# Main_Control_V1_1.net
KiCad netlist of a schematic drawn in Altium Designer
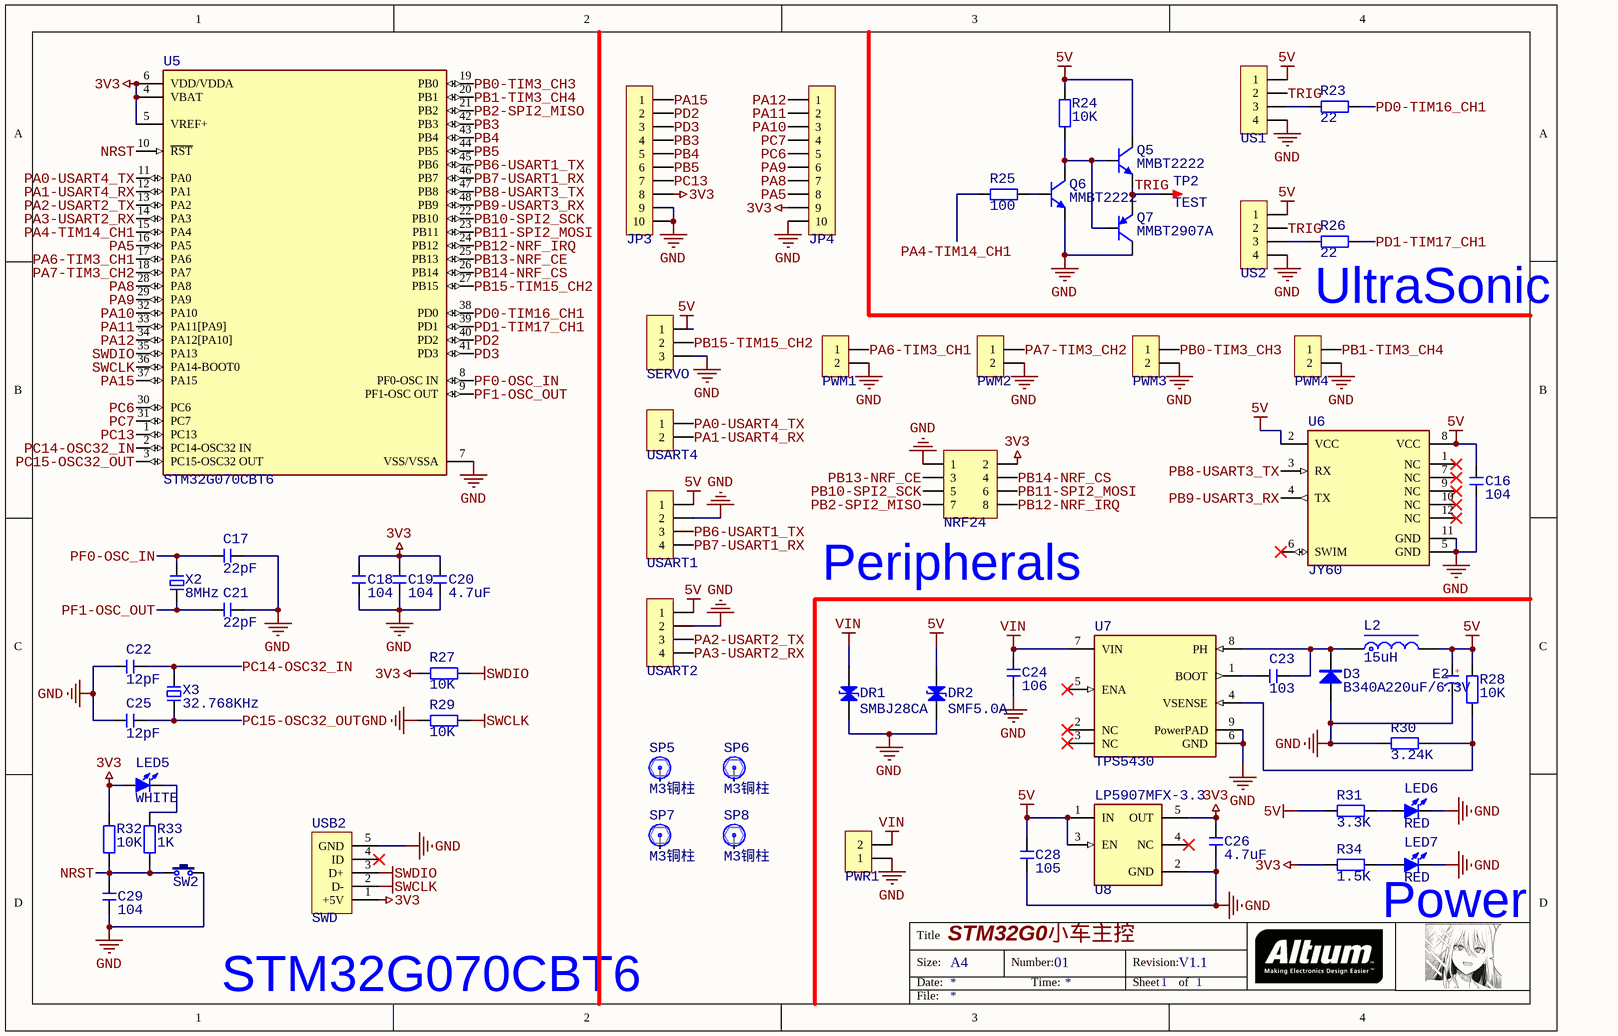
[diagram p0: Main_Control_V1.1.SchDoc]

(export (version "E")
  (design (tool "Eeschema 10.0.6"))
  (components
    (comp (ref "C16")
      (value "104")
      (footprint "C 0603_L")
      (description "无极性贴片电容")
      (libsource (lib "3.1   - 电阻-电容-电感") (part "C"))
    )
    (comp (ref "C17")
      (value "22pF")
      (footprint "C 0603_L")
      (description "无极性贴片电容")
      (libsource (lib "3.1   - 电阻-电容-电感") (part "C"))
    )
    (comp (ref "C18")
      (value "104")
      (footprint "C 0402_L")
      (description "无极性贴片电容")
      (libsource (lib "3.1   - 电阻-电容-电感") (part "C"))
    )
    (comp (ref "C19")
      (value "104")
      (footprint "C 0402_L")
      (description "无极性贴片电容")
      (libsource (lib "3.1   - 电阻-电容-电感") (part "C"))
    )
    (comp (ref "C20")
      (value "4.7uF")
      (footprint "C 0402_L")
      (description "无极性贴片电容")
      (libsource (lib "3.1   - 电阻-电容-电感") (part "C"))
    )
    (comp (ref "C21")
      (value "22pF")
      (footprint "C 0603_L")
      (description "无极性贴片电容")
      (libsource (lib "3.1   - 电阻-电容-电感") (part "C"))
    )
    (comp (ref "C22")
      (value "12pF")
      (footprint "C 0603_L")
      (description "无极性贴片电容")
      (libsource (lib "3.1   - 电阻-电容-电感") (part "C"))
    )
    (comp (ref "C23")
      (value "103")
      (footprint "C 0603_L")
      (description "无极性贴片电容")
      (libsource (lib "3.1   - 电阻-电容-电感") (part "C"))
    )
    (comp (ref "C24")
      (value "106")
      (footprint "C 0805_L")
      (description "无极性贴片电容")
      (libsource (lib "3.1   - 电阻-电容-电感") (part "C"))
    )
    (comp (ref "C25")
      (value "12pF")
      (footprint "C 0603_L")
      (description "无极性贴片电容")
      (libsource (lib "3.1   - 电阻-电容-电感") (part "C"))
    )
    (comp (ref "C26")
      (value "4.7uF")
      (footprint "C 0603_L")
      (description "无极性贴片电容")
      (libsource (lib "3.1   - 电阻-电容-电感") (part "C"))
    )
    (comp (ref "C28")
      (value "105")
      (footprint "C 0603_L")
      (description "无极性贴片电容")
      (libsource (lib "3.1   - 电阻-电容-电感") (part "C"))
    )
    (comp (ref "C29")
      (value "104")
      (footprint "C 0603_L")
      (description "无极性贴片电容")
      (libsource (lib "3.1   - 电阻-电容-电感") (part "C"))
    )
    (comp (ref "D3")
      (value "B340A")
      (footprint "SMA")
      (description "肖特基二极管")
      (libsource (lib "8.1   - 二极管-整流桥") (part "1N5819"))
    )
    (comp (ref "DR1")
      (value "SMBJ28CA")
      (footprint "Diode:SMB")
      (description "瞬态电压抑制二极管")
      (libsource (lib "8.1   - 二极管-整流桥") (part "DR"))
    )
    (comp (ref "DR2")
      (value "SMF5.0A")
      (footprint "SOD-323")
      (description "瞬态电压抑制二极管")
      (libsource (lib "8.1   - 二极管-整流桥") (part "DR"))
    )
    (comp (ref "E2")
      (value "220uF/6.3V")
      (footprint "CD B(3528)")
      (description "贴片钽电容")
      (libsource (lib "3.1   - 电阻-电容-电感") (part "C-CD"))
    )
    (comp (ref "JP3")
      (value "HDR-1X10")
      (footprint "HDR2.54-LI-10P")
      (description "10P接插件")
      (libsource (lib "4.6   - 接插件-脚距2.54") (part "Header 10"))
    )
    (comp (ref "JP4")
      (value "HDR-1X10")
      (footprint "HDR2.54-LI-10P")
      (description "10P接插件")
      (libsource (lib "") (part "Header 10_1"))
    )
    (comp (ref "L2")
      (value "15uH")
      (footprint "CDRH73")
      (description "功率屏蔽电感")
      (libsource (lib "3.1   - 电阻-电容-电感") (part "L-CDRH"))
    )
    (comp (ref "LED5")
      (value "WHITE")
      (footprint "LED 0603W")
      (description "贴片LED")
      (libsource (lib "9.1   - LED") (part "LED-SMD"))
    )
    (comp (ref "LED6")
      (value "RED")
      (footprint "LED 0603R")
      (description "贴片LED")
      (libsource (lib "9.1   - LED") (part "LED-SMD"))
    )
    (comp (ref "LED7")
      (value "RED")
      (footprint "LED 0603R")
      (description "贴片LED")
      (libsource (lib "9.1   - LED") (part "LED-SMD"))
    )
    (comp (ref "NRF24")
      (value "E01C-ML01D")
      (footprint "HDR2.54-LI-2x4P")
      (description "4*2P接插件")
      (libsource (lib "4.6   - 接插件-脚距2.54") (part "Header 4X2"))
    )
    (comp (ref "PWM1")
      (value "HDR-1X2")
      (footprint "GH1.25-LS-2P")
      (description "2P接插件")
      (libsource (lib "4.2   - 接插件-脚距1.25") (part "Header 2"))
    )
    (comp (ref "PWM2")
      (value "HDR-1X2")
      (footprint "GH1.25-LS-2P")
      (description "2P接插件")
      (libsource (lib "4.2   - 接插件-脚距1.25") (part "Header 2"))
    )
    (comp (ref "PWM3")
      (value "HDR-1X2")
      (footprint "GH1.25-LS-2P")
      (description "2P接插件")
      (libsource (lib "4.2   - 接插件-脚距1.25") (part "Header 2"))
    )
    (comp (ref "PWM4")
      (value "HDR-1X2")
      (footprint "GH1.25-LS-2P")
      (description "2P接插件")
      (libsource (lib "4.2   - 接插件-脚距1.25") (part "Header 2"))
    )
    (comp (ref "PWR1")
      (value "绿头卧式2P")
      (footprint "15EDGVM-02P-3.81mm")
      (description "3.81间距")
      (libsource (lib "Elmo接插件") (part "绿头卧式2P"))
    )
    (comp (ref "Q5")
      (value "MMBT2222")
      (footprint "SOT23-3L")
      (description "高压-NPN型")
      (libsource (lib "6.2   - 三极管") (part "MMBTA42"))
    )
    (comp (ref "Q6")
      (value "MMBT2222")
      (footprint "SOT23-3L")
      (description "高压-NPN型")
      (libsource (lib "6.2   - 三极管") (part "MMBTA42"))
    )
    (comp (ref "Q7")
      (value "MMBT2907A")
      (footprint "SOT23-3L")
      (description "高频放大-PNP型")
      (libsource (lib "6.2   - 三极管") (part "8550-SMD"))
    )
    (comp (ref "R23")
      (value "22")
      (footprint "R 0603_L")
      (description "贴片电阻")
      (libsource (lib "3.1   - 电阻-电容-电感") (part "R"))
    )
    (comp (ref "R24")
      (value "10K")
      (footprint "R 0603_L")
      (description "贴片电阻")
      (libsource (lib "3.1   - 电阻-电容-电感") (part "R"))
    )
    (comp (ref "R25")
      (value "100")
      (footprint "R 0603_L")
      (description "贴片电阻")
      (libsource (lib "3.1   - 电阻-电容-电感") (part "R"))
    )
    (comp (ref "R26")
      (value "22")
      (footprint "R 0603_L")
      (description "贴片电阻")
      (libsource (lib "3.1   - 电阻-电容-电感") (part "R"))
    )
    (comp (ref "R27")
      (value "10K")
      (footprint "R 0603_L")
      (description "贴片电阻")
      (libsource (lib "3.1   - 电阻-电容-电感") (part "R"))
    )
    (comp (ref "R28")
      (value "10K")
      (footprint "R 0603_L")
      (description "贴片电阻")
      (libsource (lib "3.1   - 电阻-电容-电感") (part "R"))
    )
    (comp (ref "R29")
      (value "10K")
      (footprint "R 0603_L")
      (description "贴片电阻")
      (libsource (lib "3.1   - 电阻-电容-电感") (part "R"))
    )
    (comp (ref "R30")
      (value "3.24K")
      (footprint "R 0603_L")
      (description "贴片电阻")
      (libsource (lib "3.1   - 电阻-电容-电感") (part "R"))
    )
    (comp (ref "R31")
      (value "3.3K")
      (footprint "R 0603_L")
      (description "贴片电阻")
      (libsource (lib "3.1   - 电阻-电容-电感") (part "R"))
    )
    (comp (ref "R32")
      (value "10K")
      (footprint "R 0603_L")
      (description "贴片电阻")
      (libsource (lib "3.1   - 电阻-电容-电感") (part "R"))
    )
    (comp (ref "R33")
      (value "1K")
      (footprint "R 0603_L")
      (description "贴片电阻")
      (libsource (lib "3.1   - 电阻-电容-电感") (part "R"))
    )
    (comp (ref "R34")
      (value "1.5K")
      (footprint "R 0603_L")
      (description "贴片电阻")
      (libsource (lib "3.1   - 电阻-电容-电感") (part "R"))
    )
    (comp (ref "SERVO")
      (value "HDR-1X3")
      (footprint "XH2.54-LS-3P")
      (description "3P接插件")
      (libsource (lib "4.6   - 接插件-脚距2.54") (part "Header 3"))
    )
    (comp (ref "SP5")
      (value "M3铜柱")
      (footprint "M3x8_L")
      (description "铜柱")
      (libsource (lib "15.1 - 未分类器件") (part "铜柱小焊盘"))
    )
    (comp (ref "SP6")
      (value "M3铜柱")
      (footprint "M3x8_L")
      (description "铜柱")
      (libsource (lib "15.1 - 未分类器件") (part "铜柱小焊盘"))
    )
    (comp (ref "SP7")
      (value "M3铜柱")
      (footprint "M3x8_L")
      (description "铜柱")
      (libsource (lib "15.1 - 未分类器件") (part "铜柱小焊盘"))
    )
    (comp (ref "SP8")
      (value "M3铜柱")
      (footprint "M3x8_L")
      (description "铜柱")
      (libsource (lib "15.1 - 未分类器件") (part "铜柱小焊盘"))
    )
    (comp (ref "SW2")
      (value "6x6x5")
      (footprint "TS 2PIN 6x6x4.8")
      (description "2脚贴片6x6无声硅胶轻触开关")
      (libsource (lib "KEY") (part "TSW SMD-2Pin-6x6"))
    )
    (comp (ref "TP2")
      (value "TEST")
      (footprint "TEST 1")
      (description "测试点")
      (libsource (lib "15.1 - 未分类器件") (part "TEST"))
    )
    (comp (ref "U5")
      (value "STM32G070CBT6")
      (footprint "STMicroelectronics_LQFP48-5B_MFG")
      (libsource (lib "高级IC") (part "STM32G070CBT6"))
    )
    (comp (ref "U6")
      (value "JY60")
      (footprint "JY60")
      (description "ICM-42605 六轴姿态测量传感器")
      (libsource (lib "Unclassified") (part "JY60"))
    )
    (comp (ref "U7")
      (value "TPS5430")
      (footprint "Texas_Instruments_DDA0008J_IPC_C")
      (description "5.5V to 36V Input, 3A, 500kHz Step-Down Converter 8-SO PowerPAD 0 to 0")
      (libsource (lib "高级IC") (part "TPS5430DDA"))
    )
    (comp (ref "U8")
      (value "LP5907MFX-3.3")
      (footprint "Diodes_SOT25_MFG")
      (description "250-mA ultra-low-noise low-IQ low-dropout (LDO) linear regulator 5-SOT-23 -40 to 125")
      (libsource (lib "高级IC") (part "LP5907MFX-3.3-NOPB"))
    )
    (comp (ref "US1")
      (value "HDR-1X4")
      (footprint "XH2.54-LS-4P")
      (description "4P接插件")
      (libsource (lib "4.6   - 接插件-脚距2.54") (part "Header 4"))
    )
    (comp (ref "US2")
      (value "HDR-1X4")
      (footprint "XH2.54-LS-4P")
      (description "4P接插件")
      (libsource (lib "4.6   - 接插件-脚距2.54") (part "Header 4"))
    )
    (comp (ref "USART1")
      (value "HDR-1X4")
      (footprint "XH2.54-LS-4P")
      (description "4P接插件")
      (libsource (lib "4.6   - 接插件-脚距2.54") (part "Header 4"))
    )
    (comp (ref "USART2")
      (value "HDR-1X4")
      (footprint "XH2.54-LS-4P")
      (description "4P接插件")
      (libsource (lib "4.6   - 接插件-脚距2.54") (part "Header 4"))
    )
    (comp (ref "USART4")
      (value "HDR-1X2")
      (footprint "XH2.54-LS-2P")
      (description "2P接插件")
      (libsource (lib "4.6   - 接插件-脚距2.54") (part "Header 2"))
    )
    (comp (ref "USB2")
      (value "SWD")
      (footprint "USB-MICRO_C")
      (description "微型USB母座")
      (libsource (lib "4.1   - 接口类") (part "USB-5P"))
    )
    (comp (ref "X2")
      (value "8MHz")
      (footprint "OSC 5032-2P")
      (description "2脚无源脚晶振")
      (libsource (lib "10.1 - 保险丝-晶振") (part "XTAL-2P"))
    )
    (comp (ref "X3")
      (value "32.768KHz")
      (footprint "OSC 3215-2P")
      (description "2脚无源脚晶振")
      (libsource (lib "10.1 - 保险丝-晶振") (part "XTAL-2P"))
    )
  )
  (nets
    (net (code "1") (name "/NRST") (class "Default")
      (node (ref "C29") (pin "2") (pinfunction "2_2") (pintype "passive"))
      (node (ref "R32") (pin "1") (pinfunction "1_1") (pintype "passive"))
      (node (ref "R33") (pin "1") (pinfunction "1_1") (pintype "passive"))
      (node (ref "SW2") (pin "1") (pinfunction "1_1") (pintype "passive"))
      (node (ref "U5") (pin "10") (pinfunction "~{RST}_10") (pintype "input"))
    )
    (net (code "2") (name "/PA0-USART4_TX") (class "Default")
      (node (ref "U5") (pin "11") (pinfunction "PA0_11") (pintype "bidirectional"))
      (node (ref "USART4") (pin "1") (pinfunction "1_1") (pintype "passive"))
    )
    (net (code "3") (name "/PA1-USART4_RX") (class "Default")
      (node (ref "U5") (pin "12") (pinfunction "PA1_12") (pintype "bidirectional"))
      (node (ref "USART4") (pin "2") (pinfunction "2_2") (pintype "passive"))
    )
    (net (code "4") (name "/PA2-USART2_TX") (class "Default")
      (node (ref "U5") (pin "13") (pinfunction "PA2_13") (pintype "bidirectional"))
      (node (ref "USART2") (pin "3") (pinfunction "3_3") (pintype "passive"))
    )
    (net (code "5") (name "/PA3-USART2_RX") (class "Default")
      (node (ref "U5") (pin "14") (pinfunction "PA3_14") (pintype "bidirectional"))
      (node (ref "USART2") (pin "4") (pinfunction "4_4") (pintype "passive"))
    )
    (net (code "6") (name "/PA4-TIM14_CH1") (class "Default")
      (node (ref "R25") (pin "1") (pinfunction "1_1") (pintype "passive"))
      (node (ref "U5") (pin "15") (pinfunction "PA4_15") (pintype "bidirectional"))
    )
    (net (code "7") (name "/PA5") (class "Default")
      (node (ref "JP4") (pin "8") (pinfunction "8_8") (pintype "passive"))
      (node (ref "U5") (pin "16") (pinfunction "PA5_16") (pintype "bidirectional"))
    )
    (net (code "8") (name "/PA6-TIM3_CH1") (class "Default")
      (node (ref "PWM1") (pin "1") (pinfunction "1_1") (pintype "passive"))
      (node (ref "U5") (pin "17") (pinfunction "PA6_17") (pintype "bidirectional"))
    )
    (net (code "9") (name "/PA7-TIM3_CH2") (class "Default")
      (node (ref "PWM2") (pin "1") (pinfunction "1_1") (pintype "passive"))
      (node (ref "U5") (pin "18") (pinfunction "PA7_18") (pintype "bidirectional"))
    )
    (net (code "10") (name "/PA8") (class "Default")
      (node (ref "JP4") (pin "7") (pinfunction "7_7") (pintype "passive"))
      (node (ref "U5") (pin "28") (pinfunction "PA8_28") (pintype "bidirectional"))
    )
    (net (code "11") (name "/PA9") (class "Default")
      (node (ref "JP4") (pin "6") (pinfunction "6_6") (pintype "passive"))
      (node (ref "U5") (pin "29") (pinfunction "PA9_29") (pintype "bidirectional"))
    )
    (net (code "12") (name "/PA10") (class "Default")
      (node (ref "JP4") (pin "3") (pinfunction "3_3") (pintype "passive"))
      (node (ref "U5") (pin "32") (pinfunction "PA10_32") (pintype "bidirectional"))
    )
    (net (code "13") (name "/PA11") (class "Default")
      (node (ref "JP4") (pin "2") (pinfunction "2_2") (pintype "passive"))
      (node (ref "U5") (pin "33") (pinfunction "PA11[PA9]_33") (pintype "bidirectional"))
    )
    (net (code "14") (name "/PA12") (class "Default")
      (node (ref "JP4") (pin "1") (pinfunction "1_1") (pintype "passive"))
      (node (ref "U5") (pin "34") (pinfunction "PA12[PA10]_34") (pintype "bidirectional"))
    )
    (net (code "15") (name "/PA15") (class "Default")
      (node (ref "JP3") (pin "1") (pinfunction "1_1") (pintype "passive"))
      (node (ref "U5") (pin "37") (pinfunction "PA15_37") (pintype "bidirectional"))
    )
    (net (code "16") (name "/PB0-TIM3_CH3") (class "Default")
      (node (ref "PWM3") (pin "1") (pinfunction "1_1") (pintype "passive"))
      (node (ref "U5") (pin "19") (pinfunction "PB0_19") (pintype "bidirectional"))
    )
    (net (code "17") (name "/PB1-TIM3_CH4") (class "Default")
      (node (ref "PWM4") (pin "1") (pinfunction "1_1") (pintype "passive"))
      (node (ref "U5") (pin "20") (pinfunction "PB1_20") (pintype "bidirectional"))
    )
    (net (code "18") (name "/PB2-SPI2_MISO") (class "Default")
      (node (ref "NRF24") (pin "7") (pinfunction "7_7") (pintype "passive"))
      (node (ref "U5") (pin "21") (pinfunction "PB2_21") (pintype "bidirectional"))
    )
    (net (code "19") (name "/PB3") (class "Default")
      (node (ref "JP3") (pin "4") (pinfunction "4_4") (pintype "passive"))
      (node (ref "U5") (pin "42") (pinfunction "PB3_42") (pintype "bidirectional"))
    )
    (net (code "20") (name "/PB4") (class "Default")
      (node (ref "JP3") (pin "5") (pinfunction "5_5") (pintype "passive"))
      (node (ref "U5") (pin "43") (pinfunction "PB4_43") (pintype "bidirectional"))
    )
    (net (code "21") (name "/PB5") (class "Default")
      (node (ref "JP3") (pin "6") (pinfunction "6_6") (pintype "passive"))
      (node (ref "U5") (pin "44") (pinfunction "PB5_44") (pintype "bidirectional"))
    )
    (net (code "22") (name "/PB6-USART1_TX") (class "Default")
      (node (ref "U5") (pin "45") (pinfunction "PB6_45") (pintype "bidirectional"))
      (node (ref "USART1") (pin "3") (pinfunction "3_3") (pintype "passive"))
    )
    (net (code "23") (name "/PB7-USART1_RX") (class "Default")
      (node (ref "U5") (pin "46") (pinfunction "PB7_46") (pintype "bidirectional"))
      (node (ref "USART1") (pin "4") (pinfunction "4_4") (pintype "passive"))
    )
    (net (code "24") (name "/PB8-USART3_TX") (class "Default")
      (node (ref "U5") (pin "47") (pinfunction "PB8_47") (pintype "bidirectional"))
      (node (ref "U6") (pin "3") (pinfunction "RX_3") (pintype "input"))
    )
    (net (code "25") (name "/PB9-USART3_RX") (class "Default")
      (node (ref "U5") (pin "48") (pinfunction "PB9_48") (pintype "bidirectional"))
      (node (ref "U6") (pin "4") (pinfunction "TX_4") (pintype "output"))
    )
    (net (code "26") (name "/PB10-SPI2_SCK") (class "Default")
      (node (ref "NRF24") (pin "5") (pinfunction "5_5") (pintype "passive"))
      (node (ref "U5") (pin "22") (pinfunction "PB10_22") (pintype "bidirectional"))
    )
    (net (code "27") (name "/PB11-SPI2_MOSI") (class "Default")
      (node (ref "NRF24") (pin "6") (pinfunction "6_6") (pintype "passive"))
      (node (ref "U5") (pin "23") (pinfunction "PB11_23") (pintype "bidirectional"))
    )
    (net (code "28") (name "/PB12-NRF_IRQ") (class "Default")
      (node (ref "NRF24") (pin "8") (pinfunction "8_8") (pintype "passive"))
      (node (ref "U5") (pin "24") (pinfunction "PB12_24") (pintype "bidirectional"))
    )
    (net (code "29") (name "/PB13-NRF_CE") (class "Default")
      (node (ref "NRF24") (pin "3") (pinfunction "3_3") (pintype "passive"))
      (node (ref "U5") (pin "25") (pinfunction "PB13_25") (pintype "bidirectional"))
    )
    (net (code "30") (name "/PB14-NRF_CS") (class "Default")
      (node (ref "NRF24") (pin "4") (pinfunction "4_4") (pintype "passive"))
      (node (ref "U5") (pin "26") (pinfunction "PB14_26") (pintype "bidirectional"))
    )
    (net (code "31") (name "/PB15-TIM15_CH2") (class "Default")
      (node (ref "SERVO") (pin "2") (pinfunction "2_2") (pintype "passive"))
      (node (ref "U5") (pin "27") (pinfunction "PB15_27") (pintype "bidirectional"))
    )
    (net (code "32") (name "/PC6") (class "Default")
      (node (ref "JP4") (pin "5") (pinfunction "5_5") (pintype "passive"))
      (node (ref "U5") (pin "30") (pinfunction "PC6_30") (pintype "bidirectional"))
    )
    (net (code "33") (name "/PC7") (class "Default")
      (node (ref "JP4") (pin "4") (pinfunction "4_4") (pintype "passive"))
      (node (ref "U5") (pin "31") (pinfunction "PC7_31") (pintype "bidirectional"))
    )
    (net (code "34") (name "/PC13") (class "Default")
      (node (ref "JP3") (pin "7") (pinfunction "7_7") (pintype "passive"))
      (node (ref "U5") (pin "1") (pinfunction "PC13_1") (pintype "bidirectional"))
    )
    (net (code "35") (name "/PC14-OSC32_IN") (class "Default")
      (node (ref "C22") (pin "1") (pinfunction "1_1") (pintype "passive"))
      (node (ref "U5") (pin "2") (pinfunction "PC14-OSC32_IN_2") (pintype "bidirectional"))
      (node (ref "X3") (pin "2") (pinfunction "2_2") (pintype "passive"))
    )
    (net (code "36") (name "/PC15-OSC32_OUT") (class "Default")
      (node (ref "C25") (pin "1") (pinfunction "1_1") (pintype "passive"))
      (node (ref "U5") (pin "3") (pinfunction "PC15-OSC32_OUT_3") (pintype "bidirectional"))
      (node (ref "X3") (pin "1") (pinfunction "1_1") (pintype "passive"))
    )
    (net (code "37") (name "/PD0-TIM16_CH1") (class "Default")
      (node (ref "R23") (pin "2") (pinfunction "2_2") (pintype "passive"))
      (node (ref "U5") (pin "38") (pinfunction "PD0_38") (pintype "bidirectional"))
    )
    (net (code "38") (name "/PD1-TIM17_CH1") (class "Default")
      (node (ref "R26") (pin "2") (pinfunction "2_2") (pintype "passive"))
      (node (ref "U5") (pin "39") (pinfunction "PD1_39") (pintype "bidirectional"))
    )
    (net (code "39") (name "/PD2") (class "Default")
      (node (ref "JP3") (pin "2") (pinfunction "2_2") (pintype "passive"))
      (node (ref "U5") (pin "40") (pinfunction "PD2_40") (pintype "bidirectional"))
    )
    (net (code "40") (name "/PD3") (class "Default")
      (node (ref "JP3") (pin "3") (pinfunction "3_3") (pintype "passive"))
      (node (ref "U5") (pin "41") (pinfunction "PD3_41") (pintype "bidirectional"))
    )
    (net (code "41") (name "/PF0-OSC_IN") (class "Default")
      (node (ref "C17") (pin "2") (pinfunction "2_2") (pintype "passive"))
      (node (ref "U5") (pin "8") (pinfunction "PF0-OSC_IN_8") (pintype "bidirectional"))
      (node (ref "X2") (pin "2") (pinfunction "2_2") (pintype "passive"))
    )
    (net (code "42") (name "/PF1-OSC_OUT") (class "Default")
      (node (ref "C21") (pin "2") (pinfunction "2_2") (pintype "passive"))
      (node (ref "U5") (pin "9") (pinfunction "PF1-OSC_OUT_9") (pintype "bidirectional"))
      (node (ref "X2") (pin "1") (pinfunction "1_1") (pintype "passive"))
    )
    (net (code "43") (name "/TRIG") (class "Default")
      (node (ref "Q5") (pin "2") (pinfunction "E_2") (pintype "passive"))
      (node (ref "Q7") (pin "2") (pinfunction "E_2") (pintype "passive"))
      (node (ref "TP2") (pin "1") (pinfunction "1_1") (pintype "passive"))
      (node (ref "US1") (pin "2") (pinfunction "2_2") (pintype "passive"))
      (node (ref "US2") (pin "2") (pinfunction "2_2") (pintype "passive"))
    )
    (net (code "44") (name "3V3") (class "Default")
      (node (ref "C18") (pin "2") (pinfunction "2_2") (pintype "passive"))
      (node (ref "C19") (pin "2") (pinfunction "2_2") (pintype "passive"))
      (node (ref "C20") (pin "2") (pinfunction "2_2") (pintype "passive"))
      (node (ref "C26") (pin "2") (pinfunction "2_2") (pintype "passive"))
      (node (ref "JP3") (pin "8") (pinfunction "8_8") (pintype "passive"))
      (node (ref "JP4") (pin "9") (pinfunction "9_9") (pintype "passive"))
      (node (ref "LED5") (pin "1") (pinfunction "A_1") (pintype "passive"))
      (node (ref "NRF24") (pin "2") (pinfunction "2_2") (pintype "passive"))
      (node (ref "R27") (pin "2") (pinfunction "2_2") (pintype "passive"))
      (node (ref "R32") (pin "2") (pinfunction "2_2") (pintype "passive"))
      (node (ref "R34") (pin "1") (pinfunction "1_1") (pintype "passive"))
      (node (ref "U5") (pin "4") (pinfunction "VBAT_4") (pintype "power_in"))
      (node (ref "U5") (pin "5") (pinfunction "VREF+_5") (pintype "power_in"))
      (node (ref "U5") (pin "6") (pinfunction "VDD/VDDA_6") (pintype "power_in"))
      (node (ref "U8") (pin "5") (pinfunction "OUT_5") (pintype "power_in"))
      (node (ref "USB2") (pin "1") (pinfunction "+5V_1") (pintype "passive"))
    )
    (net (code "45") (name "5V") (class "Default")
      (node (ref "C16") (pin "2") (pinfunction "2_2") (pintype "passive"))
      (node (ref "C28") (pin "2") (pinfunction "2_2") (pintype "passive"))
      (node (ref "DR2") (pin "2") (pinfunction "K_2") (pintype "passive"))
      (node (ref "E2") (pin "1") (pinfunction "A_1") (pintype "passive"))
      (node (ref "L2") (pin "2") (pinfunction "2_2") (pintype "passive"))
      (node (ref "Q5") (pin "3") (pinfunction "C_3") (pintype "passive"))
      (node (ref "R24") (pin "2") (pinfunction "2_2") (pintype "passive"))
      (node (ref "R28") (pin "2") (pinfunction "2_2") (pintype "passive"))
      (node (ref "R31") (pin "1") (pinfunction "1_1") (pintype "passive"))
      (node (ref "SERVO") (pin "1") (pinfunction "1_1") (pintype "passive"))
      (node (ref "U6") (pin "2") (pinfunction "VCC_2") (pintype "power_in"))
      (node (ref "U6") (pin "8") (pinfunction "VCC_8") (pintype "passive"))
      (node (ref "U8") (pin "1") (pinfunction "IN_1") (pintype "power_in"))
      (node (ref "U8") (pin "3") (pinfunction "EN_3") (pintype "input"))
      (node (ref "US1") (pin "1") (pinfunction "1_1") (pintype "passive"))
      (node (ref "US2") (pin "1") (pinfunction "1_1") (pintype "passive"))
      (node (ref "USART1") (pin "1") (pinfunction "1_1") (pintype "passive"))
      (node (ref "USART2") (pin "1") (pinfunction "1_1") (pintype "passive"))
    )
    (net (code "46") (name "GND") (class "Default")
      (node (ref "C16") (pin "1") (pinfunction "1_1") (pintype "passive"))
      (node (ref "C17") (pin "1") (pinfunction "1_1") (pintype "passive"))
      (node (ref "C18") (pin "1") (pinfunction "1_1") (pintype "passive"))
      (node (ref "C19") (pin "1") (pinfunction "1_1") (pintype "passive"))
      (node (ref "C20") (pin "1") (pinfunction "1_1") (pintype "passive"))
      (node (ref "C21") (pin "1") (pinfunction "1_1") (pintype "passive"))
      (node (ref "C22") (pin "2") (pinfunction "2_2") (pintype "passive"))
      (node (ref "C24") (pin "1") (pinfunction "1_1") (pintype "passive"))
      (node (ref "C25") (pin "2") (pinfunction "2_2") (pintype "passive"))
      (node (ref "C26") (pin "1") (pinfunction "1_1") (pintype "passive"))
      (node (ref "C28") (pin "1") (pinfunction "1_1") (pintype "passive"))
      (node (ref "C29") (pin "1") (pinfunction "1_1") (pintype "passive"))
      (node (ref "D3") (pin "1") (pinfunction "A_1") (pintype "passive"))
      (node (ref "DR1") (pin "2") (pinfunction "K_2") (pintype "passive"))
      (node (ref "DR2") (pin "1") (pinfunction "A_1") (pintype "passive"))
      (node (ref "E2") (pin "2") (pinfunction "K_2") (pintype "passive"))
      (node (ref "JP3") (pin "10") (pinfunction "10_10") (pintype "passive"))
      (node (ref "JP3") (pin "9") (pinfunction "9_9") (pintype "passive"))
      (node (ref "JP4") (pin "10") (pinfunction "10_10") (pintype "passive"))
      (node (ref "LED6") (pin "2") (pinfunction "K_2") (pintype "passive"))
      (node (ref "LED7") (pin "2") (pinfunction "K_2") (pintype "passive"))
      (node (ref "NRF24") (pin "1") (pinfunction "1_1") (pintype "passive"))
      (node (ref "PWM1") (pin "2") (pinfunction "2_2") (pintype "passive"))
      (node (ref "PWM2") (pin "2") (pinfunction "2_2") (pintype "passive"))
      (node (ref "PWM3") (pin "2") (pinfunction "2_2") (pintype "passive"))
      (node (ref "PWM4") (pin "2") (pinfunction "2_2") (pintype "passive"))
      (node (ref "PWR1") (pin "1") (pinfunction "1_1") (pintype "passive"))
      (node (ref "Q6") (pin "2") (pinfunction "E_2") (pintype "passive"))
      (node (ref "Q7") (pin "3") (pinfunction "C_3") (pintype "passive"))
      (node (ref "R29") (pin "2") (pinfunction "2_2") (pintype "passive"))
      (node (ref "R30") (pin "2") (pinfunction "2_2") (pintype "passive"))
      (node (ref "SERVO") (pin "3") (pinfunction "3_3") (pintype "passive"))
      (node (ref "SW2") (pin "2") (pinfunction "2_2") (pintype "passive"))
      (node (ref "U5") (pin "7") (pinfunction "VSS/VSSA_7") (pintype "power_in"))
      (node (ref "U6") (pin "11") (pinfunction "GND_11") (pintype "passive"))
      (node (ref "U6") (pin "5") (pinfunction "GND_5") (pintype "power_in"))
      (node (ref "U7") (pin "6") (pinfunction "GND_6") (pintype "power_in"))
      (node (ref "U7") (pin "9") (pinfunction "PowerPAD_9") (pintype "power_in"))
      (node (ref "U8") (pin "2") (pinfunction "GND_2") (pintype "power_in"))
      (node (ref "US1") (pin "4") (pinfunction "4_4") (pintype "passive"))
      (node (ref "US2") (pin "4") (pinfunction "4_4") (pintype "passive"))
      (node (ref "USART1") (pin "2") (pinfunction "2_2") (pintype "passive"))
      (node (ref "USART2") (pin "2") (pinfunction "2_2") (pintype "passive"))
      (node (ref "USB2") (pin "5") (pinfunction "GND_5") (pintype "passive"))
    )
    (net (code "47") (name "Net-(D3-K)") (class "Default")
      (node (ref "C23") (pin "1") (pinfunction "1_1") (pintype "passive"))
      (node (ref "D3") (pin "2") (pinfunction "K_2") (pintype "passive"))
      (node (ref "L2") (pin "1") (pinfunction "1_1") (pintype "passive"))
      (node (ref "U7") (pin "8") (pinfunction "PH_8") (pintype "input"))
    )
    (net (code "48") (name "Net-(LED5-K)") (class "Default")
      (node (ref "LED5") (pin "2") (pinfunction "K_2") (pintype "passive"))
      (node (ref "R33") (pin "2") (pinfunction "2_2") (pintype "passive"))
    )
    (net (code "49") (name "Net-(LED6-A)") (class "Default")
      (node (ref "LED6") (pin "1") (pinfunction "A_1") (pintype "passive"))
      (node (ref "R31") (pin "2") (pinfunction "2_2") (pintype "passive"))
    )
    (net (code "50") (name "Net-(LED7-A)") (class "Default")
      (node (ref "LED7") (pin "1") (pinfunction "A_1") (pintype "passive"))
      (node (ref "R34") (pin "2") (pinfunction "2_2") (pintype "passive"))
    )
    (net (code "51") (name "Net-(Q5-B)") (class "Default")
      (node (ref "Q5") (pin "1") (pinfunction "B_1") (pintype "passive"))
      (node (ref "Q6") (pin "3") (pinfunction "C_3") (pintype "passive"))
      (node (ref "Q7") (pin "1") (pinfunction "B_1") (pintype "passive"))
      (node (ref "R24") (pin "1") (pinfunction "1_1") (pintype "passive"))
    )
    (net (code "52") (name "Net-(Q6-B)") (class "Default")
      (node (ref "Q6") (pin "1") (pinfunction "B_1") (pintype "passive"))
      (node (ref "R25") (pin "2") (pinfunction "2_2") (pintype "passive"))
    )
    (net (code "53") (name "Net-(R23-Pad1)") (class "Default")
      (node (ref "R23") (pin "1") (pinfunction "1_1") (pintype "passive"))
      (node (ref "US1") (pin "3") (pinfunction "3_3") (pintype "passive"))
    )
    (net (code "54") (name "Net-(R26-Pad1)") (class "Default")
      (node (ref "R26") (pin "1") (pinfunction "1_1") (pintype "passive"))
      (node (ref "US2") (pin "3") (pinfunction "3_3") (pintype "passive"))
    )
    (net (code "55") (name "Net-(U7-BOOT)") (class "Default")
      (node (ref "C23") (pin "2") (pinfunction "2_2") (pintype "passive"))
      (node (ref "U7") (pin "1") (pinfunction "BOOT_1") (pintype "output"))
    )
    (net (code "56") (name "Net-(U7-VSENSE)") (class "Default")
      (node (ref "R28") (pin "1") (pinfunction "1_1") (pintype "passive"))
      (node (ref "R30") (pin "1") (pinfunction "1_1") (pintype "passive"))
      (node (ref "U7") (pin "4") (pinfunction "VSENSE_4") (pintype "input"))
    )
    (net (code "57") (name "SWCLK") (class "Default")
      (node (ref "R29") (pin "1") (pinfunction "1_1") (pintype "passive"))
      (node (ref "U5") (pin "36") (pinfunction "PA14-BOOT0_36") (pintype "bidirectional"))
      (node (ref "USB2") (pin "2") (pinfunction "D-_2") (pintype "passive"))
    )
    (net (code "58") (name "SWDIO") (class "Default")
      (node (ref "R27") (pin "1") (pinfunction "1_1") (pintype "passive"))
      (node (ref "U5") (pin "35") (pinfunction "PA13_35") (pintype "bidirectional"))
      (node (ref "USB2") (pin "3") (pinfunction "D+_3") (pintype "passive"))
    )
    (net (code "59") (name "VIN") (class "Default")
      (node (ref "C24") (pin "2") (pinfunction "2_2") (pintype "passive"))
      (node (ref "DR1") (pin "1") (pinfunction "A_1") (pintype "passive"))
      (node (ref "PWR1") (pin "2") (pinfunction "2_2") (pintype "passive"))
      (node (ref "U7") (pin "7") (pinfunction "VIN_7") (pintype "power_in"))
    )
    (net (code "60") (name "unconnected-(SP5-Pad1)") (class "Default")
      (node (ref "SP5") (pin "1") (pinfunction "1_1") (pintype "passive"))
    )
    (net (code "61") (name "unconnected-(SP6-Pad1)") (class "Default")
      (node (ref "SP6") (pin "1") (pinfunction "1_1") (pintype "passive"))
    )
    (net (code "62") (name "unconnected-(SP7-Pad1)") (class "Default")
      (node (ref "SP7") (pin "1") (pinfunction "1_1") (pintype "passive"))
    )
    (net (code "63") (name "unconnected-(SP8-Pad1)") (class "Default")
      (node (ref "SP8") (pin "1") (pinfunction "1_1") (pintype "passive"))
    )
    (net (code "64") (name "unconnected-(U6-NC-Pad1)") (class "Default")
      (node (ref "U6") (pin "1") (pinfunction "NC_1") (pintype "passive+no_connect"))
    )
    (net (code "65") (name "unconnected-(U6-NC-Pad7)") (class "Default")
      (node (ref "U6") (pin "7") (pinfunction "NC_7") (pintype "passive+no_connect"))
    )
    (net (code "66") (name "unconnected-(U6-NC-Pad9)") (class "Default")
      (node (ref "U6") (pin "9") (pinfunction "NC_9") (pintype "passive+no_connect"))
    )
    (net (code "67") (name "unconnected-(U6-NC-Pad10)") (class "Default")
      (node (ref "U6") (pin "10") (pinfunction "NC_10") (pintype "passive+no_connect"))
    )
    (net (code "68") (name "unconnected-(U6-NC-Pad12)") (class "Default")
      (node (ref "U6") (pin "12") (pinfunction "NC_12") (pintype "passive+no_connect"))
    )
    (net (code "69") (name "unconnected-(U6-SWIM-Pad6)") (class "Default")
      (node (ref "U6") (pin "6") (pinfunction "SWIM_6") (pintype "bidirectional+no_connect"))
    )
    (net (code "70") (name "unconnected-(U7-ENA-Pad5)") (class "Default")
      (node (ref "U7") (pin "5") (pinfunction "ENA_5") (pintype "input+no_connect"))
    )
    (net (code "71") (name "unconnected-(U7-NC-Pad2)") (class "Default")
      (node (ref "U7") (pin "2") (pinfunction "NC_2") (pintype "passive+no_connect"))
    )
    (net (code "72") (name "unconnected-(U7-NC-Pad3)") (class "Default")
      (node (ref "U7") (pin "3") (pinfunction "NC_3") (pintype "passive+no_connect"))
    )
    (net (code "73") (name "unconnected-(U8-NC-Pad4)") (class "Default")
      (node (ref "U8") (pin "4") (pinfunction "NC_4") (pintype "passive+no_connect"))
    )
    (net (code "74") (name "unconnected-(USB2-ID-Pad4)") (class "Default")
      (node (ref "USB2") (pin "4") (pinfunction "ID_4") (pintype "passive+no_connect"))
    )
  )
)
